# breakoutconn.net
KiCad netlist of a schematic drawn in Altium Designer
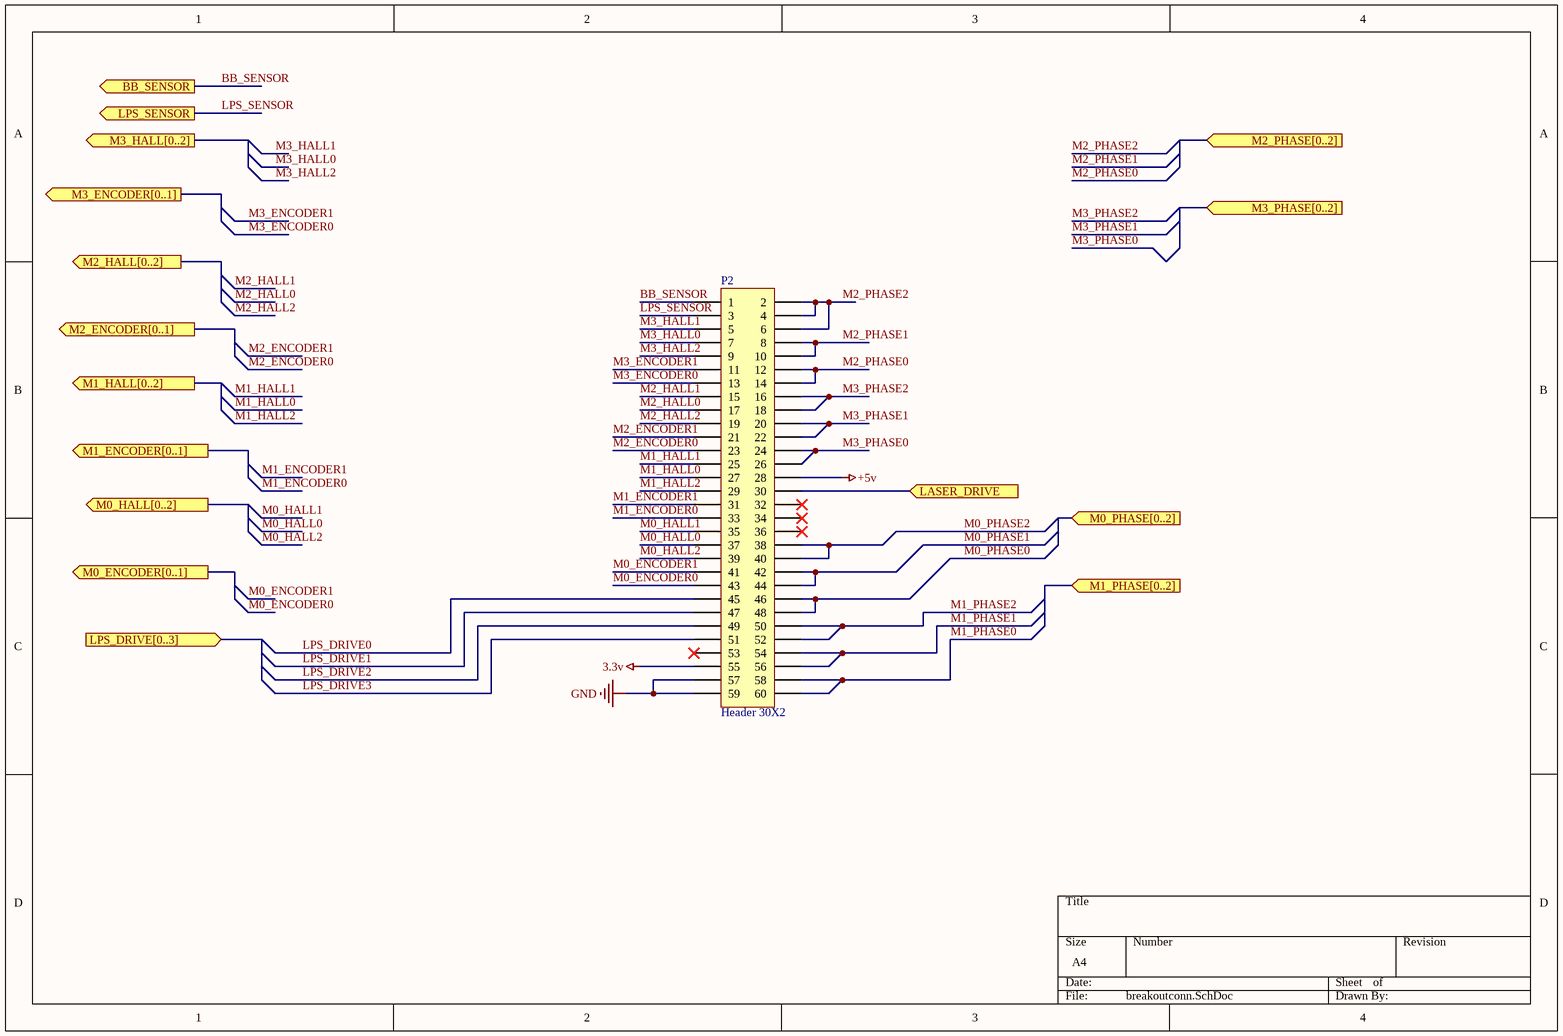
[diagram p0: breakoutconn.SchDoc]

(export (version "E")
  (design (tool "Eeschema 10.0.6"))
  (components
    (comp (ref "P2")
      (value "Header 30X2")
      (footprint "HDR2X30")
      (description "Header, 30-Pin, Dual row")
      (fields (field (name "PUBLISHER") "Altium Limited"))
      (libsource (lib "Miscellaneous Connectors") (part "Header 30X2"))
    )
  )
  (nets
    (net (code "1") (name "+5v") (class "Default")
      (node (ref "P2") (pin "28") (pinfunction "28_28") (pintype "passive"))
    )
    (net (code "2") (name "/BB_SENSOR") (class "Default")
      (node (ref "P2") (pin "1") (pinfunction "1_1") (pintype "passive"))
    )
    (net (code "3") (name "/LASER_DRIVE") (class "Default")
      (node (ref "P2") (pin "30") (pinfunction "30_30") (pintype "passive"))
    )
    (net (code "4") (name "/LPS_DRIVE0") (class "Default")
      (node (ref "P2") (pin "45") (pinfunction "45_45") (pintype "passive"))
    )
    (net (code "5") (name "/LPS_DRIVE1") (class "Default")
      (node (ref "P2") (pin "47") (pinfunction "47_47") (pintype "passive"))
    )
    (net (code "6") (name "/LPS_DRIVE2") (class "Default")
      (node (ref "P2") (pin "49") (pinfunction "49_49") (pintype "passive"))
    )
    (net (code "7") (name "/LPS_DRIVE3") (class "Default")
      (node (ref "P2") (pin "51") (pinfunction "51_51") (pintype "passive"))
    )
    (net (code "9") (name "/LPS_SENSOR") (class "Default")
      (node (ref "P2") (pin "3") (pinfunction "3_3") (pintype "passive"))
    )
    (net (code "10") (name "/M0_ENCODER0") (class "Default")
      (node (ref "P2") (pin "43") (pinfunction "43_43") (pintype "passive"))
    )
    (net (code "11") (name "/M0_ENCODER1") (class "Default")
      (node (ref "P2") (pin "41") (pinfunction "41_41") (pintype "passive"))
    )
    (net (code "13") (name "/M0_HALL0") (class "Default")
      (node (ref "P2") (pin "37") (pinfunction "37_37") (pintype "passive"))
    )
    (net (code "14") (name "/M0_HALL1") (class "Default")
      (node (ref "P2") (pin "35") (pinfunction "35_35") (pintype "passive"))
    )
    (net (code "15") (name "/M0_HALL2") (class "Default")
      (node (ref "P2") (pin "39") (pinfunction "39_39") (pintype "passive"))
    )
    (net (code "17") (name "/M0_PHASE0") (class "Default")
      (node (ref "P2") (pin "46") (pinfunction "46_46") (pintype "passive"))
      (node (ref "P2") (pin "48") (pinfunction "48_48") (pintype "passive"))
    )
    (net (code "18") (name "/M0_PHASE1") (class "Default")
      (node (ref "P2") (pin "42") (pinfunction "42_42") (pintype "passive"))
      (node (ref "P2") (pin "44") (pinfunction "44_44") (pintype "passive"))
    )
    (net (code "19") (name "/M0_PHASE2") (class "Default")
      (node (ref "P2") (pin "38") (pinfunction "38_38") (pintype "passive"))
      (node (ref "P2") (pin "40") (pinfunction "40_40") (pintype "passive"))
    )
    (net (code "21") (name "/M1_ENCODER0") (class "Default")
      (node (ref "P2") (pin "33") (pinfunction "33_33") (pintype "passive"))
    )
    (net (code "22") (name "/M1_ENCODER1") (class "Default")
      (node (ref "P2") (pin "31") (pinfunction "31_31") (pintype "passive"))
    )
    (net (code "24") (name "/M1_HALL0") (class "Default")
      (node (ref "P2") (pin "27") (pinfunction "27_27") (pintype "passive"))
    )
    (net (code "25") (name "/M1_HALL1") (class "Default")
      (node (ref "P2") (pin "25") (pinfunction "25_25") (pintype "passive"))
    )
    (net (code "26") (name "/M1_HALL2") (class "Default")
      (node (ref "P2") (pin "29") (pinfunction "29_29") (pintype "passive"))
    )
    (net (code "28") (name "/M1_PHASE0") (class "Default")
      (node (ref "P2") (pin "58") (pinfunction "58_58") (pintype "passive"))
      (node (ref "P2") (pin "60") (pinfunction "60_60") (pintype "passive"))
    )
    (net (code "29") (name "/M1_PHASE1") (class "Default")
      (node (ref "P2") (pin "54") (pinfunction "54_54") (pintype "passive"))
      (node (ref "P2") (pin "56") (pinfunction "56_56") (pintype "passive"))
    )
    (net (code "30") (name "/M1_PHASE2") (class "Default")
      (node (ref "P2") (pin "50") (pinfunction "50_50") (pintype "passive"))
      (node (ref "P2") (pin "52") (pinfunction "52_52") (pintype "passive"))
    )
    (net (code "32") (name "/M2_ENCODER0") (class "Default")
      (node (ref "P2") (pin "23") (pinfunction "23_23") (pintype "passive"))
    )
    (net (code "33") (name "/M2_ENCODER1") (class "Default")
      (node (ref "P2") (pin "21") (pinfunction "21_21") (pintype "passive"))
    )
    (net (code "35") (name "/M2_HALL0") (class "Default")
      (node (ref "P2") (pin "17") (pinfunction "17_17") (pintype "passive"))
    )
    (net (code "36") (name "/M2_HALL1") (class "Default")
      (node (ref "P2") (pin "15") (pinfunction "15_15") (pintype "passive"))
    )
    (net (code "37") (name "/M2_HALL2") (class "Default")
      (node (ref "P2") (pin "19") (pinfunction "19_19") (pintype "passive"))
    )
    (net (code "39") (name "/M2_PHASE0") (class "Default")
      (node (ref "P2") (pin "12") (pinfunction "12_12") (pintype "passive"))
      (node (ref "P2") (pin "14") (pinfunction "14_14") (pintype "passive"))
    )
    (net (code "40") (name "/M2_PHASE1") (class "Default")
      (node (ref "P2") (pin "10") (pinfunction "10_10") (pintype "passive"))
      (node (ref "P2") (pin "8") (pinfunction "8_8") (pintype "passive"))
    )
    (net (code "41") (name "/M2_PHASE2") (class "Default")
      (node (ref "P2") (pin "2") (pinfunction "2_2") (pintype "passive"))
      (node (ref "P2") (pin "4") (pinfunction "4_4") (pintype "passive"))
      (node (ref "P2") (pin "6") (pinfunction "6_6") (pintype "passive"))
    )
    (net (code "43") (name "/M3_ENCODER0") (class "Default")
      (node (ref "P2") (pin "13") (pinfunction "13_13") (pintype "passive"))
    )
    (net (code "44") (name "/M3_ENCODER1") (class "Default")
      (node (ref "P2") (pin "11") (pinfunction "11_11") (pintype "passive"))
    )
    (net (code "46") (name "/M3_HALL0") (class "Default")
      (node (ref "P2") (pin "7") (pinfunction "7_7") (pintype "passive"))
    )
    (net (code "47") (name "/M3_HALL1") (class "Default")
      (node (ref "P2") (pin "5") (pinfunction "5_5") (pintype "passive"))
    )
    (net (code "48") (name "/M3_HALL2") (class "Default")
      (node (ref "P2") (pin "9") (pinfunction "9_9") (pintype "passive"))
    )
    (net (code "50") (name "/M3_PHASE0") (class "Default")
      (node (ref "P2") (pin "24") (pinfunction "24_24") (pintype "passive"))
      (node (ref "P2") (pin "26") (pinfunction "26_26") (pintype "passive"))
    )
    (net (code "51") (name "/M3_PHASE1") (class "Default")
      (node (ref "P2") (pin "20") (pinfunction "20_20") (pintype "passive"))
      (node (ref "P2") (pin "22") (pinfunction "22_22") (pintype "passive"))
    )
    (net (code "52") (name "/M3_PHASE2") (class "Default")
      (node (ref "P2") (pin "16") (pinfunction "16_16") (pintype "passive"))
      (node (ref "P2") (pin "18") (pinfunction "18_18") (pintype "passive"))
    )
    (net (code "54") (name "3.3v") (class "Default")
      (node (ref "P2") (pin "55") (pinfunction "55_55") (pintype "passive"))
    )
    (net (code "55") (name "GND") (class "Default")
      (node (ref "P2") (pin "57") (pinfunction "57_57") (pintype "passive"))
      (node (ref "P2") (pin "59") (pinfunction "59_59") (pintype "passive"))
    )
    (net (code "56") (name "unconnected-(P2-Pad32)") (class "Default")
      (node (ref "P2") (pin "32") (pinfunction "32_32") (pintype "passive+no_connect"))
    )
    (net (code "57") (name "unconnected-(P2-Pad34)") (class "Default")
      (node (ref "P2") (pin "34") (pinfunction "34_34") (pintype "passive+no_connect"))
    )
    (net (code "58") (name "unconnected-(P2-Pad36)") (class "Default")
      (node (ref "P2") (pin "36") (pinfunction "36_36") (pintype "passive+no_connect"))
    )
    (net (code "59") (name "unconnected-(P2-Pad53)") (class "Default")
      (node (ref "P2") (pin "53") (pinfunction "53_53") (pintype "passive+no_connect"))
    )
  )
)
